# Buck_Regulator.net
KiCad netlist of a schematic drawn in EAGLE
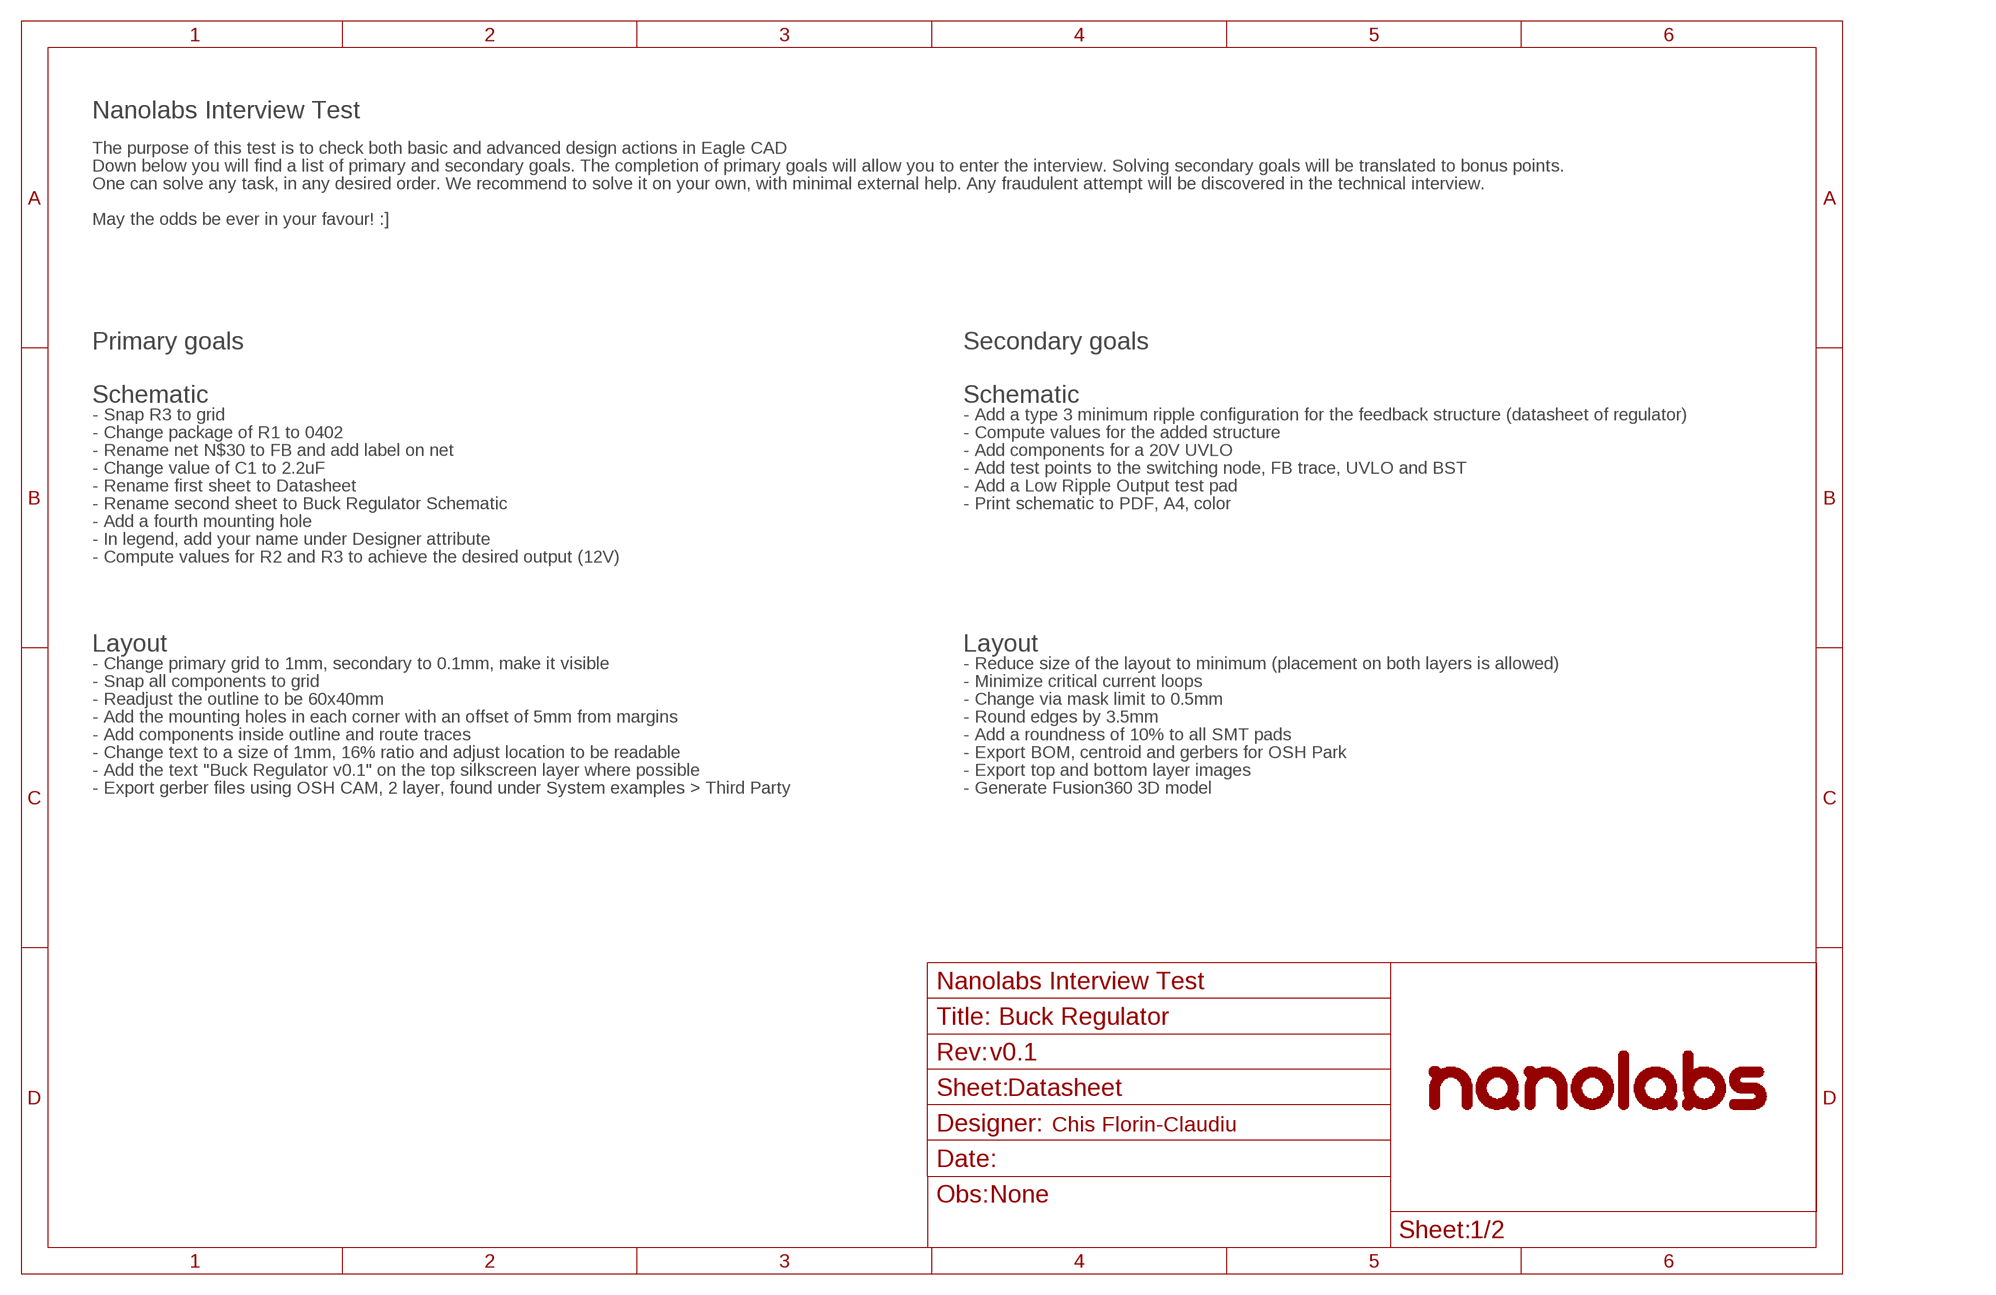
[diagram p0: schematic, sheet 1]
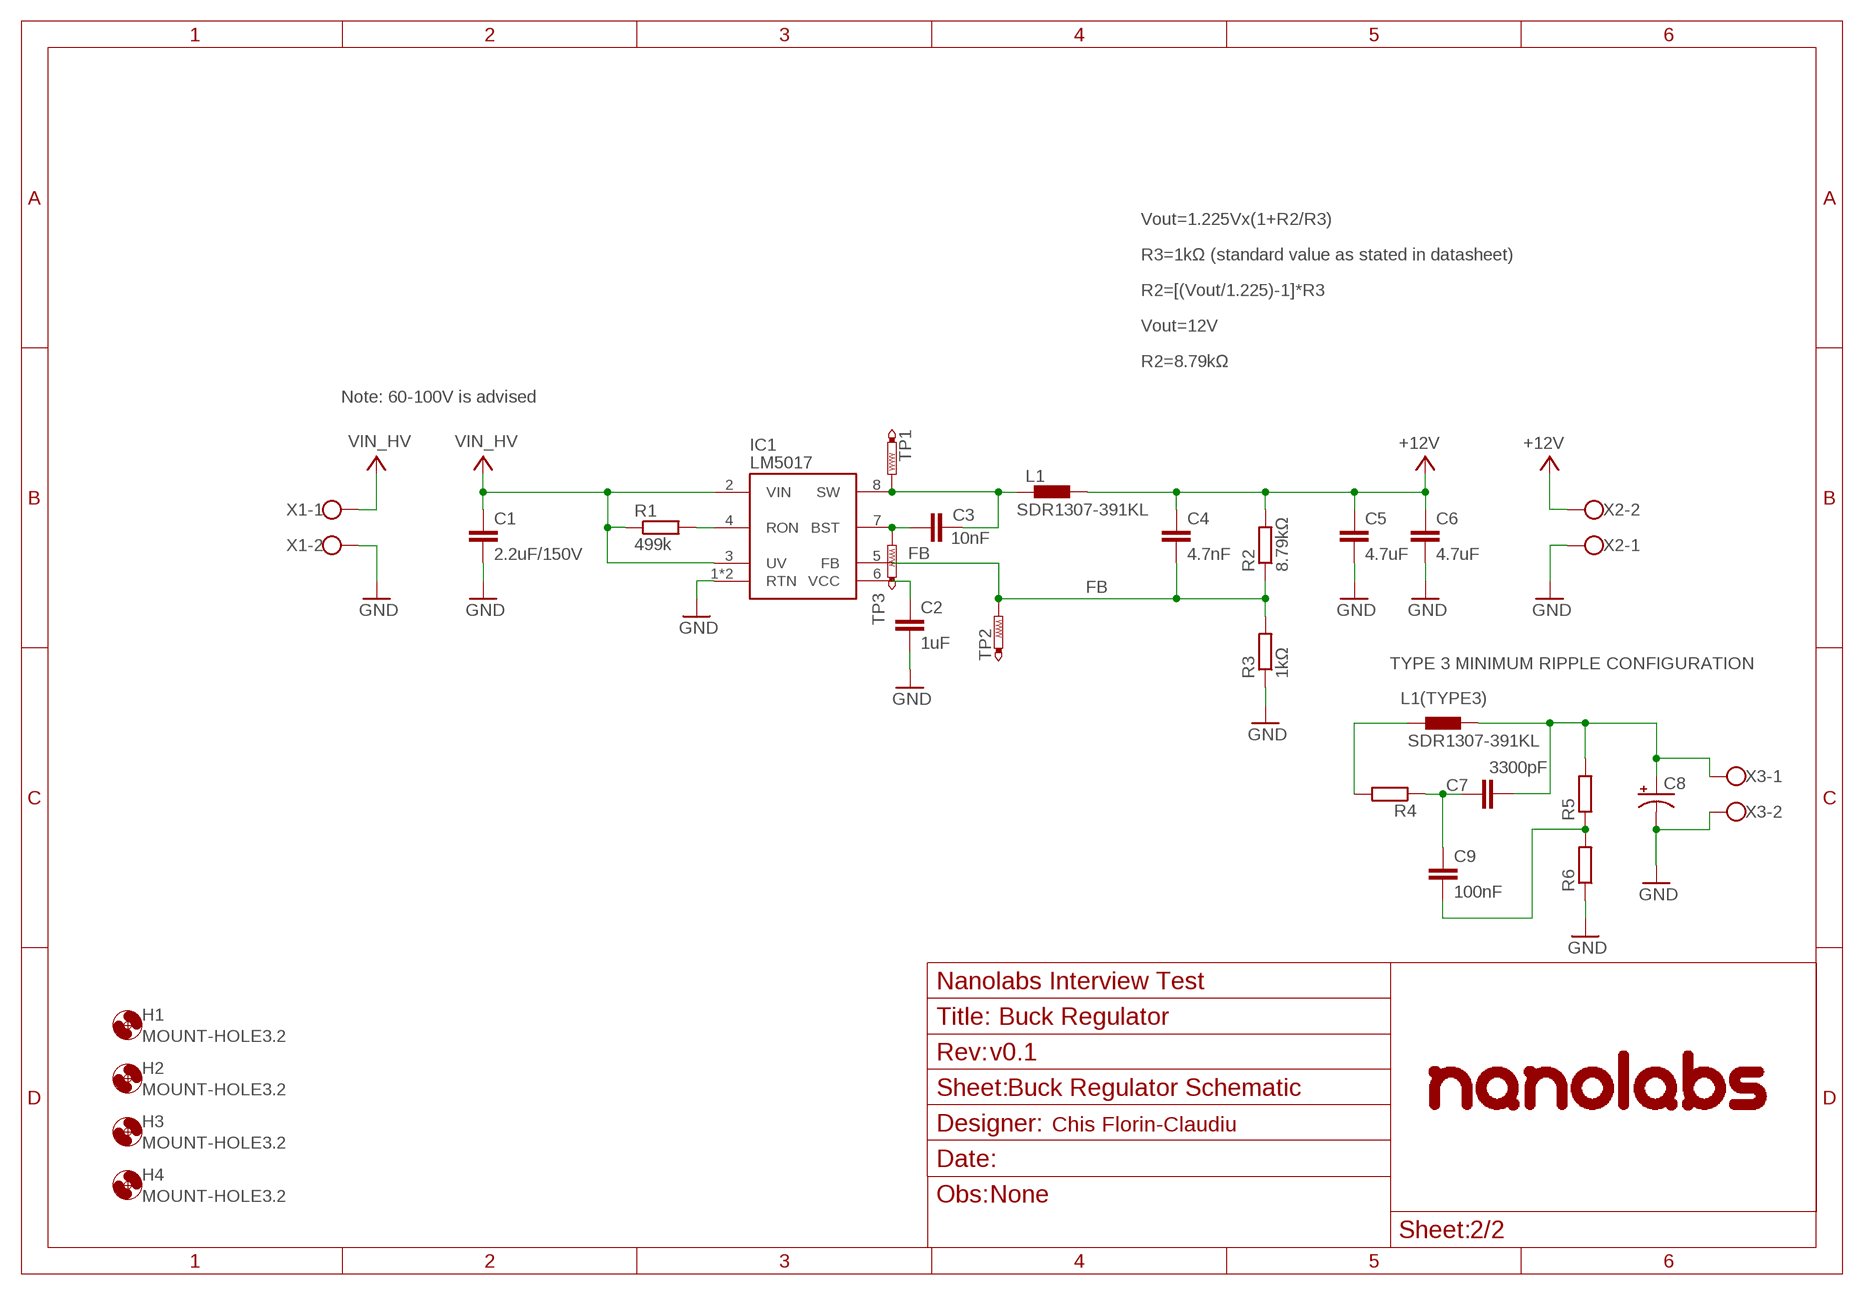
[diagram p1: schematic, sheet 2]

(export (version "E")
  (design (tool "Eeschema 10.0.6"))
  (components
    (comp (ref "C1")
      (value "2.2uF/150V")
      (footprint "eagle-import:C1812")
      (libsource (lib "eagle-import") (part "C-EUC1812"))
    )
    (comp (ref "C2")
      (value "1uF")
      (footprint "eagle-import:C0603")
      (libsource (lib "eagle-import") (part "C-EUC0603"))
    )
    (comp (ref "C3")
      (value "10nF")
      (footprint "eagle-import:C0603")
      (libsource (lib "eagle-import") (part "C-EUC0603"))
    )
    (comp (ref "C4")
      (value "4.7nF")
      (footprint "eagle-import:C0603")
      (libsource (lib "eagle-import") (part "C-EUC0603"))
    )
    (comp (ref "C5")
      (value "4.7uF")
      (footprint "eagle-import:C0603")
      (libsource (lib "eagle-import") (part "C-EUC0603"))
    )
    (comp (ref "C6")
      (value "4.7uF")
      (footprint "eagle-import:C0603")
      (libsource (lib "eagle-import") (part "C-EUC0603"))
    )
    (comp (ref "C7")
      (value "3300pF")
      (footprint "eagle-import:C0603")
      (libsource (lib "eagle-import") (part "C-EUC0603"))
    )
    (comp (ref "C8")
      (value "CPOL-US085CS-1R")
      (footprint "eagle-import:085CS_1R")
      (libsource (lib "eagle-import") (part "CPOL-US085CS-1R"))
    )
    (comp (ref "C9")
      (value "100nF")
      (footprint "eagle-import:C0603")
      (libsource (lib "eagle-import") (part "C-EUC0603"))
    )
    (comp (ref "H1")
      (value "MOUNT-HOLE3.2")
      (footprint "eagle-import:3,2")
      (libsource (lib "eagle-import") (part "MOUNT-HOLE3.2"))
    )
    (comp (ref "H2")
      (value "MOUNT-HOLE3.2")
      (footprint "eagle-import:3,2")
      (libsource (lib "eagle-import") (part "MOUNT-HOLE3.2"))
    )
    (comp (ref "H3")
      (value "MOUNT-HOLE3.2")
      (footprint "eagle-import:3,2")
      (libsource (lib "eagle-import") (part "MOUNT-HOLE3.2"))
    )
    (comp (ref "H4")
      (value "MOUNT-HOLE3.2")
      (footprint "eagle-import:3,2")
      (libsource (lib "eagle-import") (part "MOUNT-HOLE3.2"))
    )
    (comp (ref "IC1")
      (value "LM5017")
      (footprint "eagle-import:SO-08-EP")
      (libsource (lib "eagle-import") (part "LM5017"))
    )
    (comp (ref "L1")
      (value "SDR1307-391KL")
      (footprint "eagle-import:SDR1307-391KL")
      (libsource (lib "eagle-import") (part "SDR1307-391KL"))
    )
    (comp (ref "L1(TYPE3)")
      (value "SDR1307-391KL")
      (footprint "eagle-import:SDR1307-391KL")
      (libsource (lib "eagle-import") (part "SDR1307-391KL"))
    )
    (comp (ref "R1")
      (value "499k")
      (footprint "eagle-import:R0402")
      (libsource (lib "eagle-import") (part "R-EU_R0402"))
    )
    (comp (ref "R2")
      (value "8.79kΩ")
      (footprint "eagle-import:R0603")
      (libsource (lib "eagle-import") (part "R-EU_R0603"))
    )
    (comp (ref "R3")
      (value "1kΩ")
      (footprint "eagle-import:R0603")
      (libsource (lib "eagle-import") (part "R-EU_R0603"))
    )
    (comp (ref "R4")
      (value "R-EU_R0603")
      (footprint "eagle-import:R0603")
      (libsource (lib "eagle-import") (part "R-EU_R0603"))
    )
    (comp (ref "R5")
      (value "R-EU_R0603")
      (footprint "eagle-import:R0603")
      (libsource (lib "eagle-import") (part "R-EU_R0603"))
    )
    (comp (ref "R6")
      (value "R-EU_R0603")
      (footprint "eagle-import:R0603")
      (libsource (lib "eagle-import") (part "R-EU_R0603"))
    )
    (comp (ref "TP1")
      (value "PTR1PAD1-13")
      (footprint "eagle-import:P1-13")
      (libsource (lib "eagle-import") (part "PTR1PAD1-13"))
    )
    (comp (ref "TP2")
      (value "PTR1PAD1-13")
      (footprint "eagle-import:P1-13")
      (libsource (lib "eagle-import") (part "PTR1PAD1-13"))
    )
    (comp (ref "TP3")
      (value "PTR1PAD1-13")
      (footprint "eagle-import:P1-13")
      (libsource (lib "eagle-import") (part "PTR1PAD1-13"))
    )
    (comp (ref "X1")
      (value "W237-102")
      (footprint "eagle-import:W237-102")
      (fields (field (name "MPN") "237-102"))
      (libsource (lib "eagle-import") (part "W237-102"))
    )
    (comp (ref "X2")
      (value "W237-102")
      (footprint "eagle-import:W237-102")
      (fields (field (name "MPN") "237-102"))
      (libsource (lib "eagle-import") (part "W237-102"))
    )
    (comp (ref "X3")
      (value "W237-102")
      (footprint "eagle-import:W237-102")
      (fields (field (name "MPN") "237-102"))
      (libsource (lib "eagle-import") (part "W237-102"))
    )
  )
  (nets
    (net (code "1") (name "+12V") (class "Default")
      (node (ref "C4") (pin "1") (pinfunction "1_1") (pintype "passive"))
      (node (ref "C5") (pin "1") (pinfunction "1_1") (pintype "passive"))
      (node (ref "C6") (pin "1") (pinfunction "1_1") (pintype "passive"))
      (node (ref "L1") (pin "2") (pinfunction "2_2") (pintype "passive"))
      (node (ref "R2") (pin "2") (pinfunction "2_2") (pintype "passive"))
      (node (ref "X2") (pin "2") (pinfunction "KL_2") (pintype "passive"))
    )
    (net (code "2") (name "FB") (class "Default")
      (node (ref "C4") (pin "2") (pinfunction "2_2") (pintype "passive"))
      (node (ref "IC1") (pin "5") (pinfunction "FB_5") (pintype "bidirectional"))
      (node (ref "R2") (pin "1") (pinfunction "1_1") (pintype "passive"))
      (node (ref "R3") (pin "2") (pinfunction "2_2") (pintype "passive"))
      (node (ref "TP2") (pin "TP") (pinfunction "TP_TP") (pintype "input"))
    )
    (net (code "3") (name "GND") (class "Default")
      (node (ref "C1") (pin "2") (pinfunction "2_2") (pintype "passive"))
      (node (ref "C2") (pin "2") (pinfunction "2_2") (pintype "passive"))
      (node (ref "C5") (pin "2") (pinfunction "2_2") (pintype "passive"))
      (node (ref "C6") (pin "2") (pinfunction "2_2") (pintype "passive"))
      (node (ref "C8") (pin "-") (pinfunction "-_-") (pintype "passive"))
      (node (ref "IC1") (pin "1") (pinfunction "RTN_1") (pintype "bidirectional"))
      (node (ref "IC1") (pin "9") (pinfunction "RTN_9") (pintype "bidirectional"))
      (node (ref "R3") (pin "1") (pinfunction "1_1") (pintype "passive"))
      (node (ref "R6") (pin "1") (pinfunction "1_1") (pintype "passive"))
      (node (ref "X1") (pin "2") (pinfunction "KL_2") (pintype "passive"))
      (node (ref "X2") (pin "1") (pinfunction "KL_1") (pintype "passive"))
      (node (ref "X3") (pin "2") (pinfunction "KL_2") (pintype "passive"))
    )
    (net (code "4") (name "Net-(C7-Pad1)") (class "Default")
      (node (ref "C7") (pin "1") (pinfunction "1_1") (pintype "passive"))
      (node (ref "C9") (pin "1") (pinfunction "1_1") (pintype "passive"))
      (node (ref "R4") (pin "1") (pinfunction "1_1") (pintype "passive"))
    )
    (net (code "5") (name "Net-(C9-Pad2)") (class "Default")
      (node (ref "C9") (pin "2") (pinfunction "2_2") (pintype "passive"))
      (node (ref "R5") (pin "1") (pinfunction "1_1") (pintype "passive"))
      (node (ref "R6") (pin "2") (pinfunction "2_2") (pintype "passive"))
    )
    (net (code "6") (name "Net-(IC1-BST)") (class "Default")
      (node (ref "C3") (pin "1") (pinfunction "1_1") (pintype "passive"))
      (node (ref "IC1") (pin "7") (pinfunction "BST_7") (pintype "bidirectional"))
      (node (ref "TP3") (pin "TP") (pinfunction "TP_TP") (pintype "input"))
    )
    (net (code "7") (name "Net-(IC1-RON)") (class "Default")
      (node (ref "IC1") (pin "4") (pinfunction "RON_4") (pintype "bidirectional"))
      (node (ref "R1") (pin "2") (pinfunction "2_2") (pintype "passive"))
    )
    (net (code "8") (name "Net-(IC1-SW)") (class "Default")
      (node (ref "C3") (pin "2") (pinfunction "2_2") (pintype "passive"))
      (node (ref "IC1") (pin "8") (pinfunction "SW_8") (pintype "bidirectional"))
      (node (ref "L1") (pin "1") (pinfunction "1_1") (pintype "passive"))
      (node (ref "TP1") (pin "TP") (pinfunction "TP_TP") (pintype "input"))
    )
    (net (code "9") (name "Net-(IC1-VCC)") (class "Default")
      (node (ref "C2") (pin "1") (pinfunction "1_1") (pintype "passive"))
      (node (ref "IC1") (pin "6") (pinfunction "VCC_6") (pintype "bidirectional"))
    )
    (net (code "10") (name "Net-(L1(TYPE3)-Pad1)") (class "Default")
      (node (ref "L1(TYPE3)") (pin "1") (pinfunction "1_1") (pintype "passive"))
      (node (ref "R4") (pin "2") (pinfunction "2_2") (pintype "passive"))
    )
    (net (code "11") (name "Net-(X3A-KL)") (class "Default")
      (node (ref "C7") (pin "2") (pinfunction "2_2") (pintype "passive"))
      (node (ref "C8") (pin "+") (pinfunction "+_+") (pintype "passive"))
      (node (ref "L1(TYPE3)") (pin "2") (pinfunction "2_2") (pintype "passive"))
      (node (ref "R5") (pin "2") (pinfunction "2_2") (pintype "passive"))
      (node (ref "X3") (pin "1") (pinfunction "KL_1") (pintype "passive"))
    )
    (net (code "12") (name "VIN_HV") (class "Default")
      (node (ref "C1") (pin "1") (pinfunction "1_1") (pintype "passive"))
      (node (ref "IC1") (pin "2") (pinfunction "VIN_2") (pintype "bidirectional"))
      (node (ref "IC1") (pin "3") (pinfunction "UV_3") (pintype "bidirectional"))
      (node (ref "R1") (pin "1") (pinfunction "1_1") (pintype "passive"))
      (node (ref "X1") (pin "1") (pinfunction "KL_1") (pintype "passive"))
    )
  )
)
